# RS232_Level_Shifters.net
KiCad netlist of a schematic drawn in Altium Designer
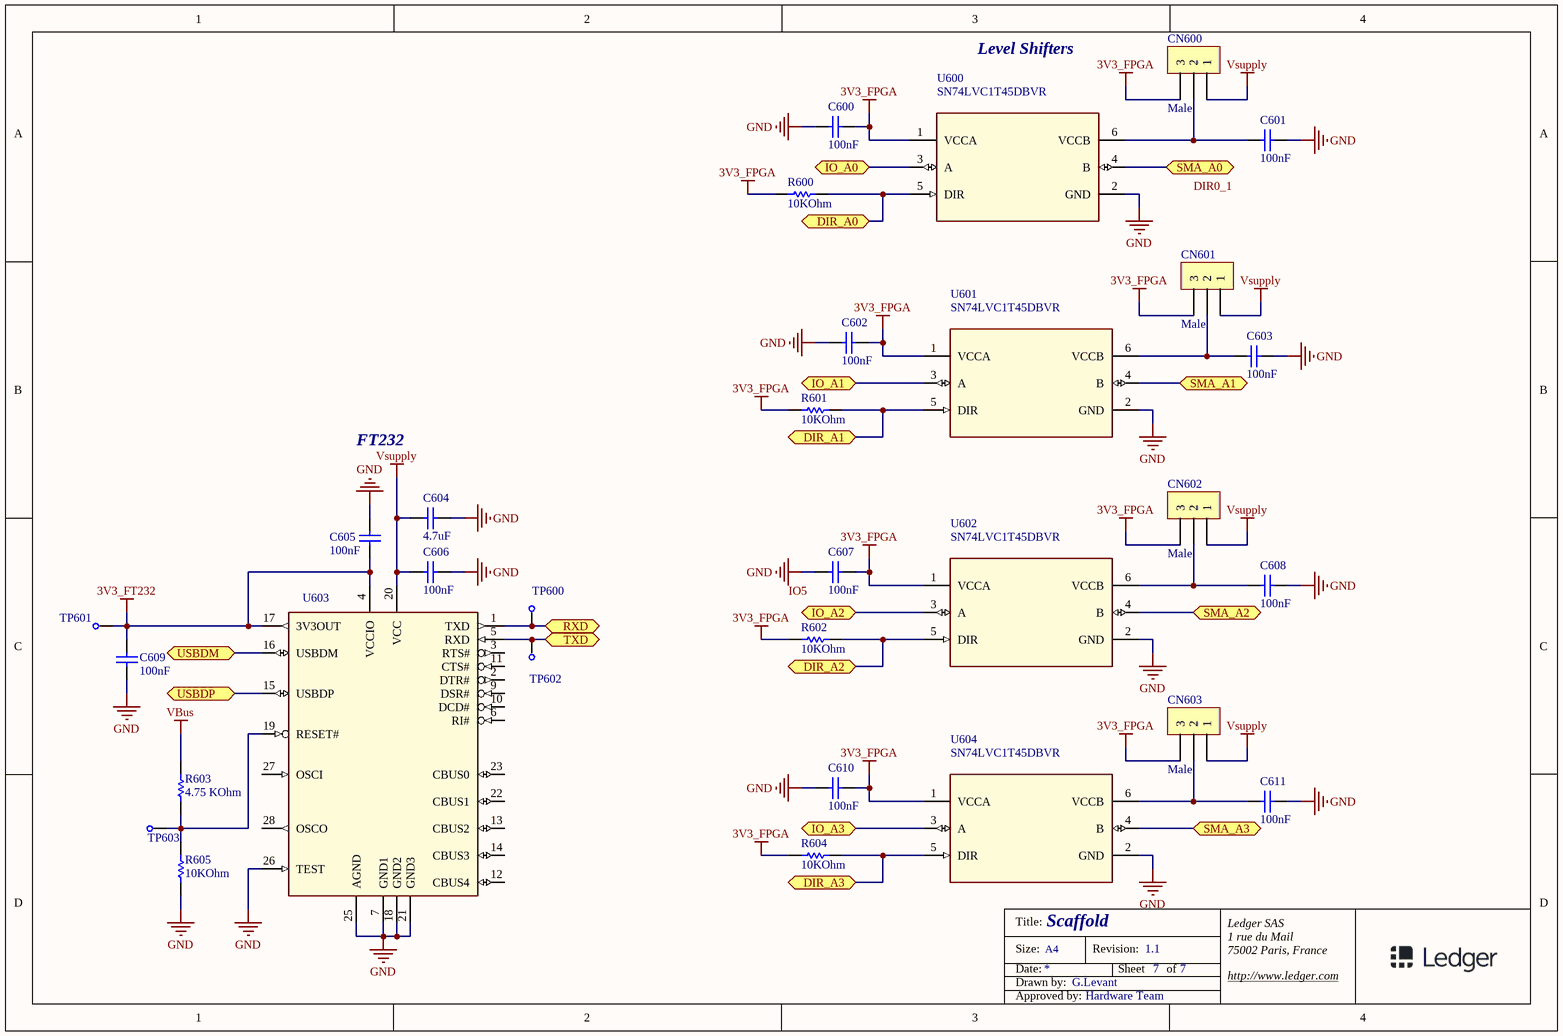
[diagram p0: RS232_Level_Shifters.SchDoc]

(export (version "E")
  (design (tool "Eeschema 10.0.6"))
  (components
    (comp (ref "C600")
      (value "100nF")
      (footprint "CAP0603")
      (description "Capacitor 0603 - 100nF - 16V - X7R - 10%")
      (fields (field (name "POWER") "16V") (field (name "TOLERANCE") "10%"))
      (libsource (lib "Ledger_Prod") (part "Capacitor 0603 - 100nF - 16V - X7R - 10%"))
    )
    (comp (ref "C601")
      (value "100nF")
      (footprint "CAP0603")
      (description "Capacitor 0603 - 100nF - 16V - X7R - 10%")
      (fields (field (name "POWER") "16V") (field (name "TOLERANCE") "10%"))
      (libsource (lib "Ledger_Prod") (part "Capacitor 0603 - 100nF - 16V - X7R - 10%"))
    )
    (comp (ref "C602")
      (value "100nF")
      (footprint "CAP0603")
      (description "Capacitor 0603 - 100nF - 16V - X7R - 10%")
      (fields (field (name "POWER") "16V") (field (name "TOLERANCE") "10%"))
      (libsource (lib "Ledger_Prod") (part "Capacitor 0603 - 100nF - 16V - X7R - 10%"))
    )
    (comp (ref "C603")
      (value "100nF")
      (footprint "CAP0603")
      (description "Capacitor 0603 - 100nF - 16V - X7R - 10%")
      (fields (field (name "POWER") "16V") (field (name "TOLERANCE") "10%"))
      (libsource (lib "Ledger_Prod") (part "Capacitor 0603 - 100nF - 16V - X7R - 10%"))
    )
    (comp (ref "C604")
      (value "4.7uF")
      (footprint "CAP0603")
      (description "Capacitor 0603 - 4.7uF - 16V - X5R - 10%")
      (fields (field (name "MANUFACTURER") "Murata") (field (name "TOLERANCE") "10%"))
      (libsource (lib "Ledger_Prod") (part "Capacitor 0603 -  4.7uF - 16V - X5R - 10%"))
    )
    (comp (ref "C605")
      (value "100nF")
      (footprint "CAP0603")
      (description "Capacitor 0603 - 100nF - 16V - X7R - 10%")
      (fields (field (name "POWER") "16V") (field (name "TOLERANCE") "10%"))
      (libsource (lib "Ledger_Prod") (part "Capacitor 0603 - 100nF - 16V - X7R - 10%"))
    )
    (comp (ref "C606")
      (value "100nF")
      (footprint "CAP0603")
      (description "Capacitor 0603 - 100nF - 16V - X7R - 10%")
      (fields (field (name "MANUFACTURER") "Wurth") (field (name "POWER") "16V"))
      (libsource (lib "Ledger_Prod") (part "Capacitor 0603 - 100nF - 16V - X7R - 10%"))
    )
    (comp (ref "C607")
      (value "100nF")
      (footprint "CAP0603")
      (description "Capacitor 0603 - 100nF - 16V - X7R - 10%")
      (fields (field (name "POWER") "16V") (field (name "TOLERANCE") "10%"))
      (libsource (lib "Ledger_Prod") (part "Capacitor 0603 - 100nF - 16V - X7R - 10%"))
    )
    (comp (ref "C608")
      (value "100nF")
      (footprint "CAP0603")
      (description "Capacitor 0603 - 100nF - 16V - X7R - 10%")
      (fields (field (name "POWER") "16V") (field (name "TOLERANCE") "10%"))
      (libsource (lib "Ledger_Prod") (part "Capacitor 0603 - 100nF - 16V - X7R - 10%"))
    )
    (comp (ref "C609")
      (value "100nF")
      (footprint "CAP0603")
      (description "Capacitor 0603 - 100nF - 16V - X7R - 10%")
      (fields (field (name "POWER") "16V") (field (name "TOLERANCE") "10%"))
      (libsource (lib "Ledger_Prod") (part "Capacitor 0603 - 100nF - 16V - X7R - 10%"))
    )
    (comp (ref "C610")
      (value "100nF")
      (footprint "CAP0603")
      (description "Capacitor 0603 - 100nF - 16V - X7R - 10%")
      (fields (field (name "POWER") "16V") (field (name "TOLERANCE") "10%"))
      (libsource (lib "Ledger_Prod") (part "Capacitor 0603 - 100nF - 16V - X7R - 10%"))
    )
    (comp (ref "C611")
      (value "100nF")
      (footprint "CAP0603")
      (description "Capacitor 0603 - 100nF - 16V - X7R - 10%")
      (fields (field (name "POWER") "16V") (field (name "TOLERANCE") "10%"))
      (libsource (lib "Ledger_Prod") (part "Capacitor 0603 - 100nF - 16V - X7R - 10%"))
    )
    (comp (ref "CN600")
      (value "Male")
      (footprint "MOLEX_90120-0123")
      (description "Connector - Header - 3-Pin - single row - Male - Molex_90120-0123")
      (fields (field (name "MANUFACTURER") "Molex"))
      (libsource (lib "Ledger_Dev") (part "Connector - Header - 3-Pin - single row - Male - Molex_90120-0123"))
    )
    (comp (ref "CN601")
      (value "Male")
      (footprint "MOLEX_90120-0123")
      (description "Connector - Header - 3-Pin - single row - Male - Molex_90120-0123")
      (fields (field (name "MANUFACTURER") "Molex"))
      (libsource (lib "Ledger_Dev") (part "Connector - Header - 3-Pin - single row - Male - Molex_90120-0123"))
    )
    (comp (ref "CN602")
      (value "Male")
      (footprint "MOLEX_90120-0123")
      (description "Connector - Header - 3-Pin - single row - Male - Molex_90120-0123")
      (fields (field (name "MANUFACTURER") "Molex"))
      (libsource (lib "Ledger_Dev") (part "Connector - Header - 3-Pin - single row - Male - Molex_90120-0123"))
    )
    (comp (ref "CN603")
      (value "Male")
      (footprint "MOLEX_90120-0123")
      (description "Connector - Header - 3-Pin - single row - Male - Molex_90120-0123")
      (fields (field (name "MANUFACTURER") "Molex"))
      (libsource (lib "Ledger_Dev") (part "Connector - Header - 3-Pin - single row - Male - Molex_90120-0123"))
    )
    (comp (ref "R600")
      (value "10KOhm")
      (footprint "RES0603")
      (description "Resistor 0603 -    10KOhm - 1/10W - 1%")
      (fields (field (name "TOLERANCE") "1%") (field (name "POWER") "1/10W"))
      (libsource (lib "Ledger_Prod") (part "Resistor 0603 -    10KOhm - 1/10W - 1%"))
    )
    (comp (ref "R601")
      (value "10KOhm")
      (footprint "RES0603")
      (description "Resistor 0603 -    10KOhm - 1/10W - 1%")
      (fields (field (name "TOLERANCE") "1%") (field (name "POWER") "1/10W"))
      (libsource (lib "Ledger_Prod") (part "Resistor 0603 -    10KOhm - 1/10W - 1%"))
    )
    (comp (ref "R602")
      (value "10KOhm")
      (footprint "RES0603")
      (description "Resistor 0603 -    10KOhm - 1/10W - 1%")
      (fields (field (name "TOLERANCE") "1%") (field (name "POWER") "1/10W"))
      (libsource (lib "Ledger_Prod") (part "Resistor 0603 -    10KOhm - 1/10W - 1%"))
    )
    (comp (ref "R603")
      (value "4.75 KOhm")
      (footprint "RES0603")
      (description "Resistor 0603 - 4.75KOhm - 1/10W - 1%")
      (fields (field (name "POWER") "1/10W") (field (name "TOLERANCE") "1%"))
      (libsource (lib "Ledger_Prod") (part "Resistor 0603 - 4.75KOhm - 1/10W - 1%"))
    )
    (comp (ref "R604")
      (value "10KOhm")
      (footprint "RES0603")
      (description "Resistor 0603 -    10KOhm - 1/10W - 1%")
      (fields (field (name "TOLERANCE") "1%") (field (name "POWER") "1/10W"))
      (libsource (lib "Ledger_Prod") (part "Resistor 0603 -    10KOhm - 1/10W - 1%"))
    )
    (comp (ref "R605")
      (value "10KOhm")
      (footprint "RES0603")
      (description "Resistor 0603 -    10KOhm - 1/10W - 1%")
      (fields (field (name "TOLERANCE") "1%") (field (name "POWER") "1/10W"))
      (libsource (lib "Ledger_Prod") (part "Resistor 0603 -    10KOhm - 1/10W - 1%"))
    )
    (comp (ref "TP600")
      (value "~")
      (footprint "TP_001")
      (description "Misc - Test point CMS")
      (libsource (lib "Ledger_Dev") (part "Misc - Test point CMS"))
    )
    (comp (ref "TP601")
      (value "~")
      (footprint "TP_001")
      (description "Misc - Test point CMS")
      (libsource (lib "Ledger_Dev") (part "Misc - Test point CMS"))
    )
    (comp (ref "TP602")
      (value "~")
      (footprint "TP_001")
      (description "Misc - Test point CMS")
      (libsource (lib "Ledger_Dev") (part "Misc - Test point CMS"))
    )
    (comp (ref "TP603")
      (value "~")
      (footprint "TP_001")
      (description "Misc - Test point CMS")
      (libsource (lib "Ledger_Dev") (part "Misc - Test point CMS"))
    )
    (comp (ref "U600")
      (value "SN74LVC1T45DBVR")
      (footprint "SOT95P280X145-6N")
      (fields (field (name "MANUFACTURER") "Texas Instruments"))
      (libsource (lib "Ledger_Dev") (part "Logic - Level Shifter - 1.65V - 5.5V - 420Mbps -3-state - SOT23-6 - Texas Instruments - SN74LVC1T45DBVR"))
    )
    (comp (ref "U601")
      (value "SN74LVC1T45DBVR")
      (footprint "SOT95P280X145-6N")
      (fields (field (name "MANUFACTURER") "Texas Instruments"))
      (libsource (lib "Ledger_Dev") (part "Logic - Level Shifter - 1.65V - 5.5V - 420Mbps -3-state - SOT23-6 - Texas Instruments - SN74LVC1T45DBVR"))
    )
    (comp (ref "U602")
      (value "SN74LVC1T45DBVR")
      (footprint "SOT95P280X145-6N")
      (fields (field (name "MANUFACTURER") "Texas Instruments"))
      (libsource (lib "Ledger_Dev") (part "Logic - Level Shifter - 1.65V - 5.5V - 420Mbps -3-state - SOT23-6 - Texas Instruments - SN74LVC1T45DBVR"))
    )
    (comp (ref "U603")
      (value "IC - USB-to-UART 1-CH 256Byte FIFO - 5V - 28-Pin SSOP")
      (footprint "SSOP28DB")
      (fields (field (name "MANUFACTURER") "FTDI"))
      (libsource (lib "Ledger_Dev") (part "IC - USB-to-UART 1-CH 256Byte FIFO - 5V - 28-Pin SSOP"))
    )
    (comp (ref "U604")
      (value "SN74LVC1T45DBVR")
      (footprint "SOT95P280X145-6N")
      (fields (field (name "MANUFACTURER") "Texas Instruments"))
      (libsource (lib "Ledger_Dev") (part "Logic - Level Shifter - 1.65V - 5.5V - 420Mbps -3-state - SOT23-6 - Texas Instruments - SN74LVC1T45DBVR"))
    )
  )
  (nets
    (net (code "2") (name "/DIR_A0") (class "Default")
      (node (ref "R600") (pin "1") (pinfunction "1_1") (pintype "passive"))
      (node (ref "U600") (pin "5") (pinfunction "DIR_5") (pintype "input"))
    )
    (net (code "3") (name "/DIR_A1") (class "Default")
      (node (ref "R601") (pin "1") (pinfunction "1_1") (pintype "passive"))
      (node (ref "U601") (pin "5") (pinfunction "DIR_5") (pintype "input"))
    )
    (net (code "4") (name "/DIR_A2") (class "Default")
      (node (ref "R602") (pin "1") (pinfunction "1_1") (pintype "passive"))
      (node (ref "U602") (pin "5") (pinfunction "DIR_5") (pintype "input"))
    )
    (net (code "5") (name "/DIR_A3") (class "Default")
      (node (ref "R604") (pin "1") (pinfunction "1_1") (pintype "passive"))
      (node (ref "U604") (pin "5") (pinfunction "DIR_5") (pintype "input"))
    )
    (net (code "7") (name "/IO_A0") (class "Default")
      (node (ref "U600") (pin "3") (pinfunction "A_3") (pintype "bidirectional"))
    )
    (net (code "8") (name "/IO_A1") (class "Default")
      (node (ref "U601") (pin "3") (pinfunction "A_3") (pintype "bidirectional"))
    )
    (net (code "9") (name "/IO_A2") (class "Default")
      (node (ref "U602") (pin "3") (pinfunction "A_3") (pintype "bidirectional"))
    )
    (net (code "10") (name "/IO_A3") (class "Default")
      (node (ref "U604") (pin "3") (pinfunction "A_3") (pintype "bidirectional"))
    )
    (net (code "11") (name "/RXD") (class "Default")
      (node (ref "TP600") (pin "1") (pinfunction "1_1") (pintype "passive"))
      (node (ref "U603") (pin "1") (pinfunction "TXD_1") (pintype "output"))
    )
    (net (code "12") (name "/SMA_A0") (class "Default")
      (node (ref "U600") (pin "4") (pinfunction "B_4") (pintype "bidirectional"))
    )
    (net (code "13") (name "/SMA_A1") (class "Default")
      (node (ref "U601") (pin "4") (pinfunction "B_4") (pintype "bidirectional"))
    )
    (net (code "14") (name "/SMA_A2") (class "Default")
      (node (ref "U602") (pin "4") (pinfunction "B_4") (pintype "bidirectional"))
    )
    (net (code "15") (name "/SMA_A3") (class "Default")
      (node (ref "U604") (pin "4") (pinfunction "B_4") (pintype "bidirectional"))
    )
    (net (code "16") (name "/TXD") (class "Default")
      (node (ref "TP602") (pin "1") (pinfunction "1_1") (pintype "passive"))
      (node (ref "U603") (pin "5") (pinfunction "RXD_5") (pintype "input"))
    )
    (net (code "17") (name "/USBDM") (class "Default")
      (node (ref "U603") (pin "16") (pinfunction "USBDM_16") (pintype "bidirectional"))
    )
    (net (code "18") (name "/USBDP") (class "Default")
      (node (ref "U603") (pin "15") (pinfunction "USBDP_15") (pintype "bidirectional"))
    )
    (net (code "19") (name "3V3_FPGA") (class "Default")
      (node (ref "C600") (pin "2") (pinfunction "2_2") (pintype "passive"))
      (node (ref "C602") (pin "2") (pinfunction "2_2") (pintype "passive"))
      (node (ref "C607") (pin "2") (pinfunction "2_2") (pintype "passive"))
      (node (ref "C610") (pin "2") (pinfunction "2_2") (pintype "passive"))
      (node (ref "CN600") (pin "3") (pinfunction "3_3") (pintype "passive"))
      (node (ref "CN601") (pin "3") (pinfunction "3_3") (pintype "passive"))
      (node (ref "CN602") (pin "3") (pinfunction "3_3") (pintype "passive"))
      (node (ref "CN603") (pin "3") (pinfunction "3_3") (pintype "passive"))
      (node (ref "R600") (pin "2") (pinfunction "2_2") (pintype "passive"))
      (node (ref "R601") (pin "2") (pinfunction "2_2") (pintype "passive"))
      (node (ref "R602") (pin "2") (pinfunction "2_2") (pintype "passive"))
      (node (ref "R604") (pin "2") (pinfunction "2_2") (pintype "passive"))
      (node (ref "U600") (pin "1") (pinfunction "VCCA_1") (pintype "power_in"))
      (node (ref "U601") (pin "1") (pinfunction "VCCA_1") (pintype "power_in"))
      (node (ref "U602") (pin "1") (pinfunction "VCCA_1") (pintype "power_in"))
      (node (ref "U604") (pin "1") (pinfunction "VCCA_1") (pintype "power_in"))
    )
    (net (code "20") (name "3V3_FT232") (class "Default")
      (node (ref "C605") (pin "1") (pinfunction "1_1") (pintype "passive"))
      (node (ref "C609") (pin "1") (pinfunction "1_1") (pintype "passive"))
      (node (ref "TP601") (pin "1") (pinfunction "1_1") (pintype "passive"))
      (node (ref "U603") (pin "17") (pinfunction "3V3OUT_17") (pintype "output"))
      (node (ref "U603") (pin "4") (pinfunction "VCCIO_4") (pintype "power_in"))
    )
    (net (code "21") (name "GND") (class "Default")
      (node (ref "C600") (pin "1") (pinfunction "1_1") (pintype "passive"))
      (node (ref "C601") (pin "1") (pinfunction "1_1") (pintype "passive"))
      (node (ref "C602") (pin "1") (pinfunction "1_1") (pintype "passive"))
      (node (ref "C603") (pin "1") (pinfunction "1_1") (pintype "passive"))
      (node (ref "C604") (pin "2") (pinfunction "2_2") (pintype "passive"))
      (node (ref "C605") (pin "2") (pinfunction "2_2") (pintype "passive"))
      (node (ref "C606") (pin "2") (pinfunction "2_2") (pintype "passive"))
      (node (ref "C607") (pin "1") (pinfunction "1_1") (pintype "passive"))
      (node (ref "C608") (pin "1") (pinfunction "1_1") (pintype "passive"))
      (node (ref "C609") (pin "2") (pinfunction "2_2") (pintype "passive"))
      (node (ref "C610") (pin "1") (pinfunction "1_1") (pintype "passive"))
      (node (ref "C611") (pin "1") (pinfunction "1_1") (pintype "passive"))
      (node (ref "R605") (pin "1") (pinfunction "1_1") (pintype "passive"))
      (node (ref "U600") (pin "2") (pinfunction "GND_2") (pintype "power_in"))
      (node (ref "U601") (pin "2") (pinfunction "GND_2") (pintype "power_in"))
      (node (ref "U602") (pin "2") (pinfunction "GND_2") (pintype "power_in"))
      (node (ref "U603") (pin "18") (pinfunction "GND2_18") (pintype "power_in"))
      (node (ref "U603") (pin "21") (pinfunction "GND3_21") (pintype "power_in"))
      (node (ref "U603") (pin "25") (pinfunction "AGND_25") (pintype "power_in"))
      (node (ref "U603") (pin "26") (pinfunction "TEST_26") (pintype "input"))
      (node (ref "U603") (pin "7") (pinfunction "GND1_7") (pintype "power_in"))
      (node (ref "U604") (pin "2") (pinfunction "GND_2") (pintype "power_in"))
    )
    (net (code "22") (name "Net-(U600-VCCB)") (class "Default")
      (node (ref "C601") (pin "2") (pinfunction "2_2") (pintype "passive"))
      (node (ref "CN600") (pin "2") (pinfunction "2_2") (pintype "passive"))
      (node (ref "U600") (pin "6") (pinfunction "VCCB_6") (pintype "power_in"))
    )
    (net (code "23") (name "Net-(U601-VCCB)") (class "Default")
      (node (ref "C603") (pin "2") (pinfunction "2_2") (pintype "passive"))
      (node (ref "CN601") (pin "2") (pinfunction "2_2") (pintype "passive"))
      (node (ref "U601") (pin "6") (pinfunction "VCCB_6") (pintype "power_in"))
    )
    (net (code "24") (name "Net-(U602-VCCB)") (class "Default")
      (node (ref "C608") (pin "2") (pinfunction "2_2") (pintype "passive"))
      (node (ref "CN602") (pin "2") (pinfunction "2_2") (pintype "passive"))
      (node (ref "U602") (pin "6") (pinfunction "VCCB_6") (pintype "power_in"))
    )
    (net (code "25") (name "Net-(U603-RESET#)") (class "Default")
      (node (ref "R603") (pin "1") (pinfunction "1_1") (pintype "passive"))
      (node (ref "R605") (pin "2") (pinfunction "2_2") (pintype "passive"))
      (node (ref "TP603") (pin "1") (pinfunction "1_1") (pintype "passive"))
      (node (ref "U603") (pin "19") (pinfunction "RESET#_19") (pintype "input"))
    )
    (net (code "26") (name "Net-(U604-VCCB)") (class "Default")
      (node (ref "C611") (pin "2") (pinfunction "2_2") (pintype "passive"))
      (node (ref "CN603") (pin "2") (pinfunction "2_2") (pintype "passive"))
      (node (ref "U604") (pin "6") (pinfunction "VCCB_6") (pintype "power_in"))
    )
    (net (code "27") (name "VBus") (class "Default")
      (node (ref "R603") (pin "2") (pinfunction "2_2") (pintype "passive"))
    )
    (net (code "28") (name "Vsupply") (class "Default")
      (node (ref "C604") (pin "1") (pinfunction "1_1") (pintype "passive"))
      (node (ref "C606") (pin "1") (pinfunction "1_1") (pintype "passive"))
      (node (ref "CN600") (pin "1") (pinfunction "1_1") (pintype "passive"))
      (node (ref "CN601") (pin "1") (pinfunction "1_1") (pintype "passive"))
      (node (ref "CN602") (pin "1") (pinfunction "1_1") (pintype "passive"))
      (node (ref "CN603") (pin "1") (pinfunction "1_1") (pintype "passive"))
      (node (ref "U603") (pin "20") (pinfunction "VCC_20") (pintype "power_in"))
    )
    (net (code "29") (name "unconnected-(U603-CBUS0-Pad23)") (class "Default")
      (node (ref "U603") (pin "23") (pinfunction "CBUS0_23") (pintype "bidirectional"))
    )
    (net (code "30") (name "unconnected-(U603-CBUS1-Pad22)") (class "Default")
      (node (ref "U603") (pin "22") (pinfunction "CBUS1_22") (pintype "bidirectional"))
    )
    (net (code "31") (name "unconnected-(U603-CBUS2-Pad13)") (class "Default")
      (node (ref "U603") (pin "13") (pinfunction "CBUS2_13") (pintype "bidirectional"))
    )
    (net (code "32") (name "unconnected-(U603-CBUS3-Pad14)") (class "Default")
      (node (ref "U603") (pin "14") (pinfunction "CBUS3_14") (pintype "bidirectional"))
    )
    (net (code "33") (name "unconnected-(U603-CBUS4-Pad12)") (class "Default")
      (node (ref "U603") (pin "12") (pinfunction "CBUS4_12") (pintype "bidirectional"))
    )
    (net (code "34") (name "unconnected-(U603-CTS#-Pad11)") (class "Default")
      (node (ref "U603") (pin "11") (pinfunction "CTS#_11") (pintype "input"))
    )
    (net (code "35") (name "unconnected-(U603-DCD#-Pad10)") (class "Default")
      (node (ref "U603") (pin "10") (pinfunction "DCD#_10") (pintype "input"))
    )
    (net (code "36") (name "unconnected-(U603-DSR#-Pad9)") (class "Default")
      (node (ref "U603") (pin "9") (pinfunction "DSR#_9") (pintype "input"))
    )
    (net (code "37") (name "unconnected-(U603-DTR#-Pad2)") (class "Default")
      (node (ref "U603") (pin "2") (pinfunction "DTR#_2") (pintype "output"))
    )
    (net (code "38") (name "unconnected-(U603-OSCI-Pad27)") (class "Default")
      (node (ref "U603") (pin "27") (pinfunction "OSCI_27") (pintype "input"))
    )
    (net (code "39") (name "unconnected-(U603-OSCO-Pad28)") (class "Default")
      (node (ref "U603") (pin "28") (pinfunction "OSCO_28") (pintype "output"))
    )
    (net (code "40") (name "unconnected-(U603-RI#-Pad6)") (class "Default")
      (node (ref "U603") (pin "6") (pinfunction "RI#_6") (pintype "input"))
    )
    (net (code "41") (name "unconnected-(U603-RTS#-Pad3)") (class "Default")
      (node (ref "U603") (pin "3") (pinfunction "RTS#_3") (pintype "output"))
    )
  )
)
